# HumTempSensor.net
KiCad netlist of a schematic drawn in Altium Designer
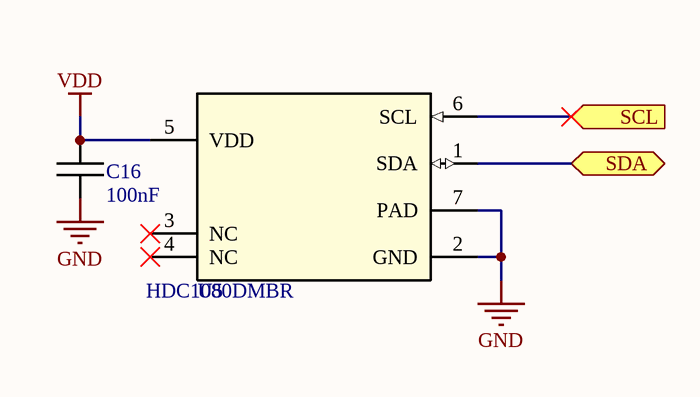
[diagram p0: HumTempSensor.SchDoc]

(export (version "E")
  (design (tool "Eeschema 10.0.6"))
  (components
    (comp (ref "C16")
      (value "100nF")
      (footprint "CAP0805")
      (description "Multilayer Ceramic Capacitor, 0.1 uF, 50 V, ± 10%, X7R, 0805 [2012 Metric]")
      (fields
        (field (name "MANUFACTURER") "Yageo")
        (field (name "MANUFACTURER PART NUMBER") "CC0805KRX7R9BB104")
      )
      (libsource (lib "Schlib1") (part "CC0805KRX7R9BB104"))
    )
    (comp (ref "U5")
      (value "HDC1080DMBR")
      (footprint "WSON_DMB6")
      (description "SENSOR HUMI/TEMP 3.3V I2C 4% SMD")
      (fields (field (name "MANUFACTURER") "Texas Instruments") (field (name "LCSC PART#") "C82227"))
      (libsource (lib "Schlib1") (part "HDC1080DMBR"))
    )
  )
  (nets
    (net (code "1") (name "/SCL") (class "Default")
      (node (ref "U5") (pin "6") (pinfunction "SCL_6") (pintype "input+no_connect"))
    )
    (net (code "2") (name "/SDA") (class "Default")
      (node (ref "U5") (pin "1") (pinfunction "SDA_1") (pintype "bidirectional"))
    )
    (net (code "3") (name "GND") (class "Default")
      (node (ref "C16") (pin "2") (pinfunction "2_2") (pintype "passive"))
      (node (ref "U5") (pin "2") (pinfunction "GND_2") (pintype "power_in"))
      (node (ref "U5") (pin "7") (pinfunction "PAD_7") (pintype "power_in"))
    )
    (net (code "4") (name "VDD") (class "Default")
      (node (ref "C16") (pin "1") (pinfunction "1_1") (pintype "passive"))
      (node (ref "U5") (pin "5") (pinfunction "VDD_5") (pintype "power_in"))
    )
    (net (code "5") (name "unconnected-(U5-NC-Pad3)") (class "Default")
      (node (ref "U5") (pin "3") (pinfunction "NC_3") (pintype "passive+no_connect"))
    )
    (net (code "6") (name "unconnected-(U5-NC-Pad4)") (class "Default")
      (node (ref "U5") (pin "4") (pinfunction "NC_4") (pintype "passive+no_connect"))
    )
  )
)
